# SCH_Flight-Computer-V5_2024-08-09.net
KiCad netlist of a schematic drawn in EasyEDA
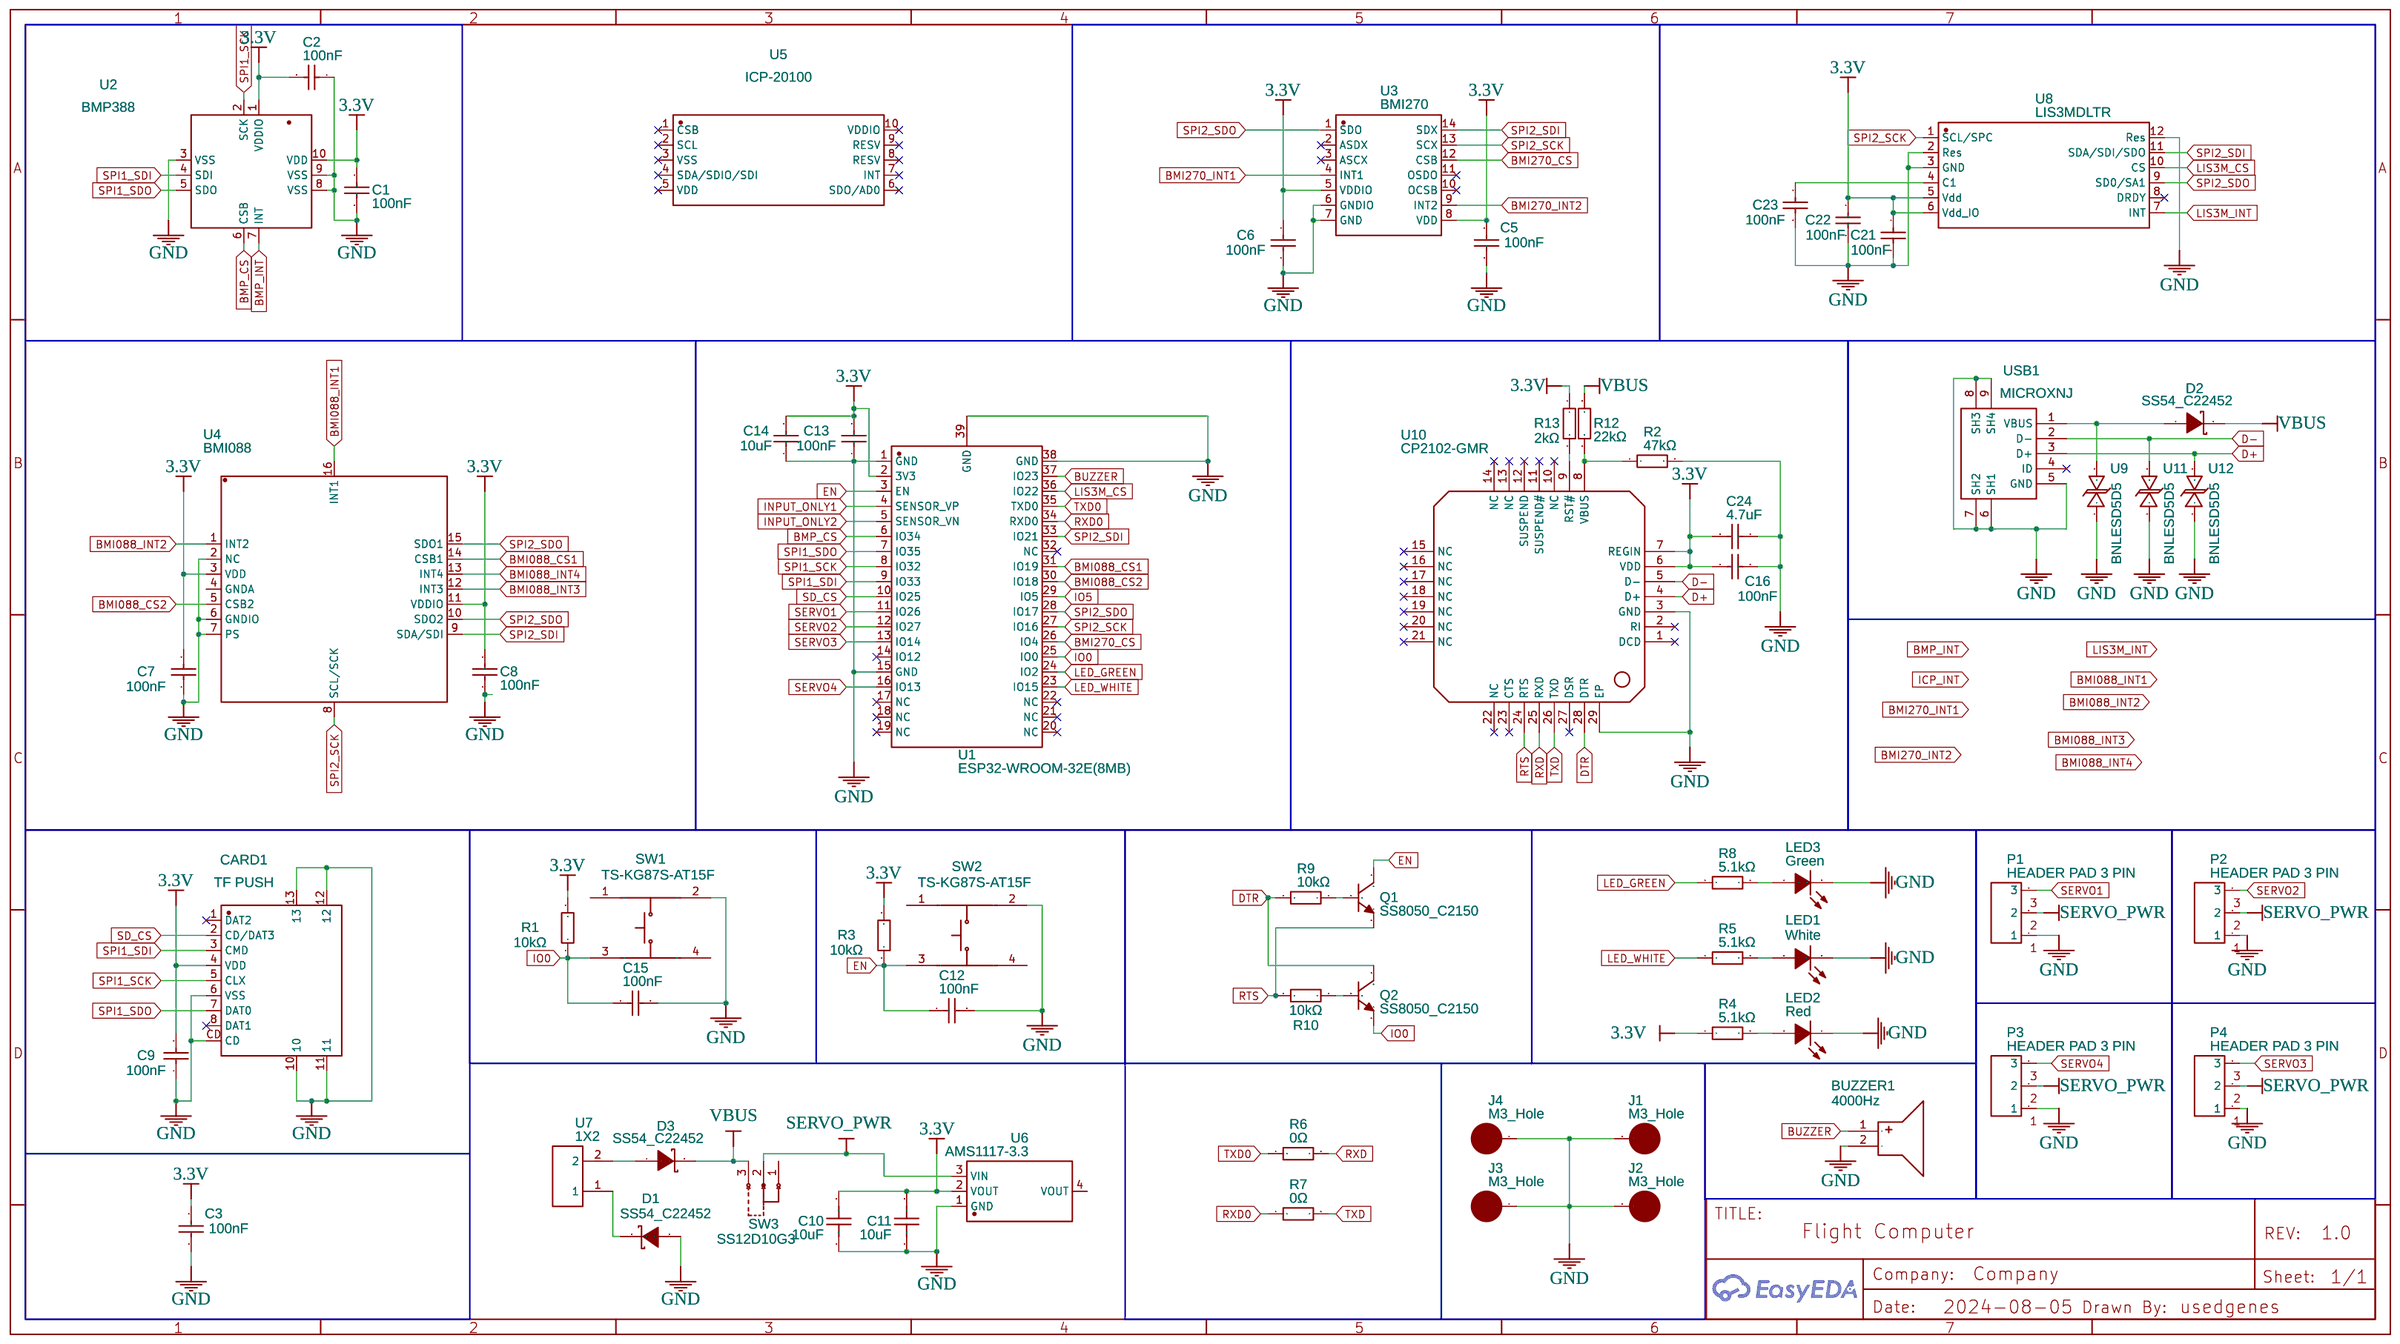
[diagram p0: schematic sheet]

(export (version "E")
  (design (tool "Eeschema 10.0.6"))
  (components
    (comp (ref "BUZZER1")
      (value "4000Hz")
      (fields
        (field (name "Manufacturer Part") "SKY-1475-0540-45P7.6")
        (field (name "Manufacturer") "S&S(海旭)")
      )
      (libsource (lib "") (part "SKY-1475-0540-45P7.6"))
    )
    (comp (ref "C1")
      (value "100nF")
      (fields
        (field (name "Manufacturer Part") "CL05B104KO5NNNC")
        (field (name "Manufacturer") "SAMSUNG(三星)")
      )
      (libsource (lib "") (part "CL05B104KO5NNNC_1"))
    )
    (comp (ref "C2")
      (value "100nF")
      (fields
        (field (name "Manufacturer Part") "CL05B104KO5NNNC")
        (field (name "Manufacturer") "SAMSUNG(三星)")
      )
      (libsource (lib "") (part "CL05B104KO5NNNC_3"))
    )
    (comp (ref "C3")
      (value "100nF")
      (fields
        (field (name "Manufacturer Part") "CL05B104KO5NNNC")
        (field (name "Manufacturer") "SAMSUNG(三星)")
      )
      (libsource (lib "") (part "CL05B104KO5NNNC_1"))
    )
    (comp (ref "C5")
      (value "100nF")
      (fields
        (field (name "Manufacturer Part") "CL05B104KO5NNNC")
        (field (name "Manufacturer") "SAMSUNG(三星)")
      )
      (libsource (lib "") (part "CL05B104KO5NNNC_1"))
    )
    (comp (ref "C6")
      (value "100nF")
      (fields
        (field (name "Manufacturer Part") "CL05B104KO5NNNC")
        (field (name "Manufacturer") "SAMSUNG(三星)")
      )
      (libsource (lib "") (part "CL05B104KO5NNNC_1"))
    )
    (comp (ref "C7")
      (value "100nF")
      (fields
        (field (name "Manufacturer Part") "CL05B104KO5NNNC")
        (field (name "Manufacturer") "SAMSUNG(三星)")
      )
      (libsource (lib "") (part "CL05B104KO5NNNC_1"))
    )
    (comp (ref "C8")
      (value "100nF")
      (fields
        (field (name "Manufacturer Part") "CL05B104KO5NNNC")
        (field (name "Manufacturer") "SAMSUNG(三星)")
      )
      (libsource (lib "") (part "CL05B104KO5NNNC_1"))
    )
    (comp (ref "C9")
      (value "100nF")
      (fields
        (field (name "Manufacturer Part") "CL05B104KO5NNNC")
        (field (name "Manufacturer") "SAMSUNG(三星)")
      )
      (libsource (lib "") (part "CL05B104KO5NNNC_1"))
    )
    (comp (ref "C10")
      (value "10uF")
      (fields
        (field (name "Manufacturer Part") "CL10A106KP8NNNC")
        (field (name "Manufacturer") "SAMSUNG(三星)")
      )
      (libsource (lib "") (part "CL10A106KP8NNNC"))
    )
    (comp (ref "C11")
      (value "10uF")
      (fields
        (field (name "Manufacturer Part") "CL10A106KP8NNNC")
        (field (name "Manufacturer") "SAMSUNG(三星)")
      )
      (libsource (lib "") (part "CL10A106KP8NNNC"))
    )
    (comp (ref "C12")
      (value "100nF")
      (fields
        (field (name "Manufacturer Part") "CL05B104KO5NNNC")
        (field (name "Manufacturer") "SAMSUNG(三星)")
      )
      (libsource (lib "") (part "CL05B104KO5NNNC_2"))
    )
    (comp (ref "C13")
      (value "100nF")
      (fields
        (field (name "Manufacturer Part") "CL05B104KO5NNNC")
        (field (name "Manufacturer") "SAMSUNG(三星)")
      )
      (libsource (lib "") (part "CL05B104KO5NNNC_1"))
    )
    (comp (ref "C14")
      (value "10uF")
      (fields
        (field (name "Manufacturer Part") "CL05A106MQ5NUNC")
        (field (name "Manufacturer") "SAMSUNG(三星)")
      )
      (libsource (lib "") (part "CL05A106MQ5NUNC"))
    )
    (comp (ref "C15")
      (value "100nF")
      (fields
        (field (name "Manufacturer Part") "CL05B104KO5NNNC")
        (field (name "Manufacturer") "SAMSUNG(三星)")
      )
      (libsource (lib "") (part "CL05B104KO5NNNC_2"))
    )
    (comp (ref "C16")
      (value "100nF")
      (fields
        (field (name "Manufacturer Part") "CL05B104KO5NNNC")
        (field (name "Manufacturer") "SAMSUNG(三星)")
      )
      (libsource (lib "") (part "CL05B104KO5NNNC_2"))
    )
    (comp (ref "C21")
      (value "100nF")
      (fields
        (field (name "Manufacturer Part") "CL05B104KO5NNNC")
        (field (name "Manufacturer") "SAMSUNG(三星)")
      )
      (libsource (lib "") (part "CL05B104KO5NNNC"))
    )
    (comp (ref "C22")
      (value "100nF")
      (fields
        (field (name "Manufacturer Part") "CL05B104KO5NNNC")
        (field (name "Manufacturer") "SAMSUNG(三星)")
      )
      (libsource (lib "") (part "CL05B104KO5NNNC"))
    )
    (comp (ref "C23")
      (value "100nF")
      (fields
        (field (name "Manufacturer Part") "CL05B104KO5NNNC")
        (field (name "Manufacturer") "SAMSUNG(三星)")
      )
      (libsource (lib "") (part "CL05B104KO5NNNC"))
    )
    (comp (ref "C24")
      (value "4.7uF")
      (fields
        (field (name "Manufacturer Part") "CL05A475MP5NRNC")
        (field (name "Manufacturer") "SAMSUNG(三星)")
      )
      (libsource (lib "") (part "CL05A475MP5NRNC"))
    )
    (comp (ref "CARD1")
      (value "TF PUSH")
      (fields (field (name "Manufacturer") "SHOU HAN(首韩)"))
      (libsource (lib "") (part "TF PUSH"))
    )
    (comp (ref "D1")
      (value "SS54_C22452")
      (fields (field (name "Manufacturer Part") "SS54") (field (name "Manufacturer") "MDD(辰达半导体)"))
      (libsource (lib "") (part "SS54_C22452"))
    )
    (comp (ref "D2")
      (value "SS54_C22452")
      (fields (field (name "Manufacturer Part") "SS54") (field (name "Manufacturer") "MDD(辰达半导体)"))
      (libsource (lib "") (part "SS54_C22452_1"))
    )
    (comp (ref "D3")
      (value "SS54_C22452")
      (fields (field (name "Manufacturer Part") "SS54") (field (name "Manufacturer") "MDD(辰达半导体)"))
      (libsource (lib "") (part "SS54_C22452_1"))
    )
    (comp (ref "J1") (value "M3_Hole") (libsource (lib "") (part "SCREW-MOUNTING-HOLE-3MM")))
    (comp (ref "J2") (value "M3_Hole") (libsource (lib "") (part "SCREW-MOUNTING-HOLE-3MM")))
    (comp (ref "J3") (value "M3_Hole") (libsource (lib "") (part "SCREW-MOUNTING-HOLE-3MM_1")))
    (comp (ref "J4") (value "M3_Hole") (libsource (lib "") (part "SCREW-MOUNTING-HOLE-3MM_1")))
    (comp (ref "LED1")
      (value "White")
      (fields (field (name "Manufacturer Part") "KT-0603白灯") (field (name "Manufacturer") "KENTO"))
      (libsource (lib "") (part "0603White light_C2290"))
    )
    (comp (ref "LED2")
      (value "Red")
      (fields (field (name "Manufacturer Part") "KT-0603R") (field (name "Manufacturer") "KENTO"))
      (libsource (lib "") (part "KT-0603R"))
    )
    (comp (ref "LED3")
      (value "Green")
      (fields (field (name "Manufacturer Part") "KT-0805G") (field (name "Manufacturer") "KENTO"))
      (libsource (lib "") (part "0805G (Green)"))
    )
    (comp (ref "P1")
      (value "HEADER PAD 3 PIN")
      (fields
        (field (name "Manufacturer Part") "Female headerHDR1X8-2.54")
        (field (name "Manufacturer") "BOOMELE")
      )
      (libsource (lib "") (part "HEADER PAD 3 PIN"))
    )
    (comp (ref "P2")
      (value "HEADER PAD 3 PIN")
      (fields
        (field (name "Manufacturer Part") "Female headerHDR1X8-2.54")
        (field (name "Manufacturer") "BOOMELE")
      )
      (libsource (lib "") (part "HEADER PAD 3 PIN"))
    )
    (comp (ref "P3")
      (value "HEADER PAD 3 PIN")
      (fields
        (field (name "Manufacturer Part") "Female headerHDR1X8-2.54")
        (field (name "Manufacturer") "BOOMELE")
      )
      (libsource (lib "") (part "HEADER PAD 3 PIN"))
    )
    (comp (ref "P4")
      (value "HEADER PAD 3 PIN")
      (fields
        (field (name "Manufacturer Part") "Female headerHDR1X8-2.54")
        (field (name "Manufacturer") "BOOMELE")
      )
      (libsource (lib "") (part "HEADER PAD 3 PIN"))
    )
    (comp (ref "Q1")
      (value "SS8050_C2150")
      (fields (field (name "Manufacturer Part") "SS8050") (field (name "Manufacturer") "CJ(江苏长电/长晶)"))
      (libsource (lib "") (part "SS8050_C2150"))
    )
    (comp (ref "Q2")
      (value "SS8050_C2150")
      (fields (field (name "Manufacturer Part") "SS8050") (field (name "Manufacturer") "CJ(江苏长电/长晶)"))
      (libsource (lib "") (part "SS8050_C2150"))
    )
    (comp (ref "R1")
      (value "10kΩ")
      (fields
        (field (name "Manufacturer Part") "0603WAF1002T5E")
        (field (name "Manufacturer") "UNI-ROYAL(厚声)")
      )
      (libsource (lib "") (part "0603WAF1002T5E_1"))
    )
    (comp (ref "R2")
      (value "47kΩ")
      (fields
        (field (name "Manufacturer Part") "0402WGF4702TCE")
        (field (name "Manufacturer") "UNI-ROYAL(厚声)")
      )
      (libsource (lib "") (part "0402WGF4702TCE"))
    )
    (comp (ref "R3")
      (value "10kΩ")
      (fields
        (field (name "Manufacturer Part") "0603WAF1002T5E")
        (field (name "Manufacturer") "UNI-ROYAL(厚声)")
      )
      (libsource (lib "") (part "0603WAF1002T5E_1"))
    )
    (comp (ref "R4")
      (value "5.1kΩ")
      (fields
        (field (name "Manufacturer Part") "0402WGF5101TCE")
        (field (name "Manufacturer") "UNI-ROYAL(厚声)")
      )
      (libsource (lib "") (part "0402WGF5101TCE"))
    )
    (comp (ref "R5")
      (value "5.1kΩ")
      (fields
        (field (name "Manufacturer Part") "0402WGF5101TCE")
        (field (name "Manufacturer") "UNI-ROYAL(厚声)")
      )
      (libsource (lib "") (part "0402WGF5101TCE"))
    )
    (comp (ref "R6")
      (value "0Ω")
      (fields
        (field (name "Manufacturer Part") "1206W4F0000T5E")
        (field (name "Manufacturer") "UNI-ROYAL(厚声)")
      )
      (libsource (lib "") (part "1206W4F0000T5E"))
    )
    (comp (ref "R7")
      (value "0Ω")
      (fields
        (field (name "Manufacturer Part") "1206W4F0000T5E")
        (field (name "Manufacturer") "UNI-ROYAL(厚声)")
      )
      (libsource (lib "") (part "1206W4F0000T5E"))
    )
    (comp (ref "R8")
      (value "5.1kΩ")
      (fields
        (field (name "Manufacturer Part") "0402WGF5101TCE")
        (field (name "Manufacturer") "UNI-ROYAL(厚声)")
      )
      (libsource (lib "") (part "0402WGF5101TCE"))
    )
    (comp (ref "R9")
      (value "10kΩ")
      (fields
        (field (name "Manufacturer Part") "0603WAF1002T5E")
        (field (name "Manufacturer") "UNI-ROYAL(厚声)")
      )
      (libsource (lib "") (part "0603WAF1002T5E_2"))
    )
    (comp (ref "R10")
      (value "10kΩ")
      (fields
        (field (name "Manufacturer Part") "0603WAF1002T5E")
        (field (name "Manufacturer") "UNI-ROYAL(厚声)")
      )
      (libsource (lib "") (part "0603WAF1002T5E"))
    )
    (comp (ref "R12")
      (value "22kΩ")
      (fields
        (field (name "Manufacturer Part") "0402WGF2202TCE")
        (field (name "Manufacturer") "UNI-ROYAL(厚声)")
      )
      (libsource (lib "") (part "0402WGF2202TCE"))
    )
    (comp (ref "R13")
      (value "2kΩ")
      (fields
        (field (name "Manufacturer Part") "0402WGF2001TCE")
        (field (name "Manufacturer") "UNI-ROYAL(厚声)")
      )
      (libsource (lib "") (part "0402WGF2001TCE"))
    )
    (comp (ref "SW1")
      (value "TS-KG87S-AT15F")
      (fields (field (name "Manufacturer") "HANBO(汉博)"))
      (libsource (lib "") (part "TS-KG87S-AT15F"))
    )
    (comp (ref "SW2")
      (value "TS-KG87S-AT15F")
      (fields (field (name "Manufacturer") "HANBO(汉博)"))
      (libsource (lib "") (part "TS-KG87S-AT15F"))
    )
    (comp (ref "SW3")
      (value "SS12D10G3")
      (fields (field (name "Manufacturer") "SHOU HAN(首韩)"))
      (libsource (lib "") (part "SS12D10G3"))
    )
    (comp (ref "U1")
      (value "ESP32-WROOM-32E(8MB)")
      (fields
        (field (name "Manufacturer Part") "ESP32-WROOM-32E-N8")
        (field (name "Manufacturer") "ESPRESSIF(乐鑫)")
      )
      (libsource (lib "") (part "ESP32-WROOM-32E(8MB)"))
    )
    (comp (ref "U2")
      (value "BMP388")
      (fields (field (name "Manufacturer") "Bosch(博世)"))
      (libsource (lib "") (part "BMP388"))
    )
    (comp (ref "U3")
      (value "BMI270")
      (fields (field (name "Manufacturer") "Bosch(博世)"))
      (libsource (lib "") (part "BMI270"))
    )
    (comp (ref "U4")
      (value "BMI088")
      (fields (field (name "Manufacturer") "Bosch(博世)"))
      (libsource (lib "") (part "BMI088"))
    )
    (comp (ref "U5")
      (value "ICP-20100")
      (fields (field (name "Manufacturer") "TDK"))
      (libsource (lib "") (part "ICP-20100"))
    )
    (comp (ref "U6")
      (value "AMS1117-3.3")
      (fields (field (name "Manufacturer") "AMS"))
      (libsource (lib "") (part "AMS1117-3.3"))
    )
    (comp (ref "U7") (value "1X2") (libsource (lib "") (part "1X2")))
    (comp (ref "U8")
      (value "LIS3MDLTR")
      (fields (field (name "Manufacturer") "ST(意法半导体)"))
      (libsource (lib "") (part "LIS3MDLTR"))
    )
    (comp (ref "U9")
      (value "BNLESD5D5")
      (fields
        (field (name "Manufacturer Part") "BNLESD5D5.0CT1G")
        (field (name "Manufacturer") "BORN(伯恩半导体)")
      )
      (libsource (lib "") (part "BNLESD5D5.0CT1G"))
    )
    (comp (ref "U10")
      (value "CP2102-GMR")
      (fields (field (name "Manufacturer") "SKYWORKS/SILICON LABS(芯科)"))
      (libsource (lib "") (part "CP2102-GMR"))
    )
    (comp (ref "U11")
      (value "BNLESD5D5")
      (fields
        (field (name "Manufacturer Part") "BNLESD5D5.0CT1G")
        (field (name "Manufacturer") "BORN(伯恩半导体)")
      )
      (libsource (lib "") (part "BNLESD5D5.0CT1G"))
    )
    (comp (ref "U12")
      (value "BNLESD5D5")
      (fields
        (field (name "Manufacturer Part") "BNLESD5D5.0CT1G")
        (field (name "Manufacturer") "BORN(伯恩半导体)")
      )
      (libsource (lib "") (part "BNLESD5D5.0CT1G"))
    )
    (comp (ref "USB1")
      (value "MICROXNJ")
      (fields (field (name "Manufacturer Part") "MicroXNJ") (field (name "Manufacturer") "SHOU HAN(首韩)"))
      (libsource (lib "") (part "MICROXNJ"))
    )
  )
  (nets
    (net (code "1") (name "3.3V") (class "Default")
      (node (ref "C1") (pin "2") (pinfunction "2_2") (pintype "input"))
      (node (ref "C10") (pin "2") (pinfunction "2_2") (pintype "unspecified"))
      (node (ref "C11") (pin "2") (pinfunction "2_2") (pintype "unspecified"))
      (node (ref "C13") (pin "2") (pinfunction "2_2") (pintype "input"))
      (node (ref "C14") (pin "2") (pinfunction "2_2") (pintype "input"))
      (node (ref "C16") (pin "1") (pinfunction "1_1") (pintype "input"))
      (node (ref "C2") (pin "2") (pinfunction "2_2") (pintype "input"))
      (node (ref "C21") (pin "1") (pinfunction "1_1") (pintype "input"))
      (node (ref "C22") (pin "1") (pinfunction "1_1") (pintype "input"))
      (node (ref "C24") (pin "1") (pinfunction "1_1") (pintype "input"))
      (node (ref "C3") (pin "2") (pinfunction "2_2") (pintype "input"))
      (node (ref "C5") (pin "2") (pinfunction "2_2") (pintype "input"))
      (node (ref "C6") (pin "2") (pinfunction "2_2") (pintype "input"))
      (node (ref "C7") (pin "2") (pinfunction "2_2") (pintype "input"))
      (node (ref "C8") (pin "2") (pinfunction "2_2") (pintype "input"))
      (node (ref "C9") (pin "2") (pinfunction "2_2") (pintype "input"))
      (node (ref "CARD1") (pin "4") (pinfunction "VDD_4") (pintype "unspecified"))
      (node (ref "R1") (pin "2") (pinfunction "2_2") (pintype "input"))
      (node (ref "R13") (pin "1") (pinfunction "1_1") (pintype "input"))
      (node (ref "R3") (pin "2") (pinfunction "2_2") (pintype "input"))
      (node (ref "R4") (pin "1") (pinfunction "1_1") (pintype "input"))
      (node (ref "U1") (pin "2") (pinfunction "3V3_2") (pintype "unspecified"))
      (node (ref "U10") (pin "6") (pinfunction "VDD_6") (pintype "unspecified"))
      (node (ref "U10") (pin "7") (pinfunction "REGIN_7") (pintype "unspecified"))
      (node (ref "U2") (pin "1") (pinfunction "VDDIO_1") (pintype "unspecified"))
      (node (ref "U2") (pin "10") (pinfunction "VDD_10") (pintype "unspecified"))
      (node (ref "U3") (pin "5") (pinfunction "VDDIO_5") (pintype "unspecified"))
      (node (ref "U3") (pin "8") (pinfunction "VDD_8") (pintype "unspecified"))
      (node (ref "U4") (pin "11") (pinfunction "VDDIO_11") (pintype "unspecified"))
      (node (ref "U4") (pin "3") (pinfunction "VDD_3") (pintype "unspecified"))
      (node (ref "U6") (pin "2") (pinfunction "VOUT_2") (pintype "unspecified"))
      (node (ref "U8") (pin "5") (pinfunction "Vdd_5") (pintype "unspecified"))
      (node (ref "U8") (pin "6") (pinfunction "Vdd_IO_6") (pintype "unspecified"))
    )
    (net (code "2") (name "BMI088_CS1") (class "Default")
      (node (ref "U1") (pin "31") (pinfunction "IO19_31") (pintype "unspecified"))
      (node (ref "U4") (pin "14") (pinfunction "CSB1_14") (pintype "unspecified"))
    )
    (net (code "3") (name "BMI088_CS2") (class "Default")
      (node (ref "U1") (pin "30") (pinfunction "IO18_30") (pintype "unspecified"))
      (node (ref "U4") (pin "5") (pinfunction "CSB2_5") (pintype "unspecified"))
    )
    (net (code "4") (name "BMI088_INT1") (class "Default")
      (node (ref "U4") (pin "16") (pinfunction "INT1_16") (pintype "unspecified"))
    )
    (net (code "5") (name "BMI088_INT2") (class "Default")
      (node (ref "U4") (pin "1") (pinfunction "INT2_1") (pintype "unspecified"))
    )
    (net (code "6") (name "BMI088_INT3") (class "Default")
      (node (ref "U4") (pin "12") (pinfunction "INT3_12") (pintype "unspecified"))
    )
    (net (code "7") (name "BMI088_INT4") (class "Default")
      (node (ref "U4") (pin "13") (pinfunction "INT4_13") (pintype "unspecified"))
    )
    (net (code "8") (name "BMI270_CS") (class "Default")
      (node (ref "U1") (pin "26") (pinfunction "IO4_26") (pintype "unspecified"))
      (node (ref "U3") (pin "12") (pinfunction "CSB_12") (pintype "unspecified"))
    )
    (net (code "9") (name "BMI270_INT1") (class "Default")
      (node (ref "U3") (pin "4") (pinfunction "INT1_4") (pintype "unspecified"))
    )
    (net (code "10") (name "BMI270_INT2") (class "Default")
      (node (ref "U3") (pin "9") (pinfunction "INT2_9") (pintype "unspecified"))
    )
    (net (code "11") (name "BMP_CS") (class "Default")
      (node (ref "U1") (pin "6") (pinfunction "IO34_6") (pintype "unspecified"))
      (node (ref "U2") (pin "6") (pinfunction "CSB_6") (pintype "unspecified"))
    )
    (net (code "12") (name "BMP_INT") (class "Default")
      (node (ref "U2") (pin "7") (pinfunction "INT_7") (pintype "unspecified"))
    )
    (net (code "13") (name "BUZZER") (class "Default")
      (node (ref "BUZZER1") (pin "1") (pinfunction "+_1") (pintype "unspecified"))
      (node (ref "U1") (pin "37") (pinfunction "IO23_37") (pintype "unspecified"))
    )
    (net (code "14") (name "D+") (class "Default")
      (node (ref "U10") (pin "4") (pinfunction "D+_4") (pintype "unspecified"))
      (node (ref "U12") (pin "2") (pinfunction "2_2") (pintype "unspecified"))
      (node (ref "USB1") (pin "3") (pinfunction "D+_3") (pintype "unspecified"))
    )
    (net (code "15") (name "D-") (class "Default")
      (node (ref "U10") (pin "5") (pinfunction "D-_5") (pintype "unspecified"))
      (node (ref "U11") (pin "2") (pinfunction "2_2") (pintype "unspecified"))
      (node (ref "USB1") (pin "2") (pinfunction "D-_2") (pintype "unspecified"))
    )
    (net (code "16") (name "DTR") (class "Default")
      (node (ref "Q2") (pin "3") (pinfunction "C_3") (pintype "unspecified"))
      (node (ref "R9") (pin "2") (pinfunction "2_2") (pintype "input"))
      (node (ref "U10") (pin "28") (pinfunction "DTR_28") (pintype "unspecified"))
    )
    (net (code "17") (name "EN") (class "Default")
      (node (ref "C12") (pin "1") (pinfunction "1_1") (pintype "input"))
      (node (ref "Q1") (pin "3") (pinfunction "C_3") (pintype "unspecified"))
      (node (ref "R3") (pin "1") (pinfunction "1_1") (pintype "input"))
      (node (ref "SW2") (pin "3") (pinfunction "3_3") (pintype "unspecified"))
      (node (ref "U1") (pin "3") (pinfunction "EN_3") (pintype "unspecified"))
    )
    (net (code "18") (name "GND") (class "Default")
      (node (ref "BUZZER1") (pin "2") (pinfunction "-_2") (pintype "unspecified"))
      (node (ref "C1") (pin "1") (pinfunction "1_1") (pintype "input"))
      (node (ref "C10") (pin "1") (pinfunction "1_1") (pintype "unspecified"))
      (node (ref "C11") (pin "1") (pinfunction "1_1") (pintype "unspecified"))
      (node (ref "C12") (pin "2") (pinfunction "2_2") (pintype "input"))
      (node (ref "C13") (pin "1") (pinfunction "1_1") (pintype "input"))
      (node (ref "C14") (pin "1") (pinfunction "1_1") (pintype "input"))
      (node (ref "C15") (pin "2") (pinfunction "2_2") (pintype "input"))
      (node (ref "C16") (pin "2") (pinfunction "2_2") (pintype "input"))
      (node (ref "C2") (pin "1") (pinfunction "1_1") (pintype "input"))
      (node (ref "C21") (pin "2") (pinfunction "2_2") (pintype "input"))
      (node (ref "C22") (pin "2") (pinfunction "2_2") (pintype "input"))
      (node (ref "C23") (pin "2") (pinfunction "2_2") (pintype "input"))
      (node (ref "C24") (pin "2") (pinfunction "2_2") (pintype "input"))
      (node (ref "C3") (pin "1") (pinfunction "1_1") (pintype "input"))
      (node (ref "C5") (pin "1") (pinfunction "1_1") (pintype "input"))
      (node (ref "C6") (pin "1") (pinfunction "1_1") (pintype "input"))
      (node (ref "C7") (pin "1") (pinfunction "1_1") (pintype "input"))
      (node (ref "C8") (pin "1") (pinfunction "1_1") (pintype "input"))
      (node (ref "C9") (pin "1") (pinfunction "1_1") (pintype "input"))
      (node (ref "CARD1") (pin "10") (pinfunction "10_10") (pintype "unspecified"))
      (node (ref "CARD1") (pin "11") (pinfunction "11_11") (pintype "unspecified"))
      (node (ref "CARD1") (pin "12") (pinfunction "12_12") (pintype "unspecified"))
      (node (ref "CARD1") (pin "13") (pinfunction "13_13") (pintype "unspecified"))
      (node (ref "CARD1") (pin "6") (pinfunction "VSS_6") (pintype "unspecified"))
      (node (ref "CARD1") (pin "CD") (pinfunction "CD_CD") (pintype "unspecified"))
      (node (ref "D1") (pin "1") (pinfunction "A_1") (pintype "unspecified"))
      (node (ref "J1") (pin "1") (pinfunction "1_1") (pintype "unspecified"))
      (node (ref "J2") (pin "1") (pinfunction "1_1") (pintype "unspecified"))
      (node (ref "J3") (pin "1") (pinfunction "1_1") (pintype "unspecified"))
      (node (ref "J4") (pin "1") (pinfunction "1_1") (pintype "unspecified"))
      (node (ref "LED1") (pin "2") (pinfunction "K_2") (pintype "unspecified"))
      (node (ref "LED2") (pin "1") (pinfunction "K_1") (pintype "unspecified"))
      (node (ref "LED3") (pin "2") (pinfunction "K_2") (pintype "unspecified"))
      (node (ref "P1") (pin "1") (pinfunction "1_1") (pintype "unspecified"))
      (node (ref "P2") (pin "1") (pinfunction "1_1") (pintype "unspecified"))
      (node (ref "P3") (pin "1") (pinfunction "1_1") (pintype "unspecified"))
      (node (ref "P4") (pin "1") (pinfunction "1_1") (pintype "unspecified"))
      (node (ref "R2") (pin "2") (pinfunction "2_2") (pintype "input"))
      (node (ref "SW1") (pin "2") (pinfunction "2_2") (pintype "unspecified"))
      (node (ref "SW2") (pin "2") (pinfunction "2_2") (pintype "unspecified"))
      (node (ref "U1") (pin "1") (pinfunction "GND_1") (pintype "unspecified"))
      (node (ref "U1") (pin "15") (pinfunction "GND_15") (pintype "unspecified"))
      (node (ref "U1") (pin "38") (pinfunction "GND_38") (pintype "unspecified"))
      (node (ref "U1") (pin "39") (pinfunction "GND_39") (pintype "unspecified"))
      (node (ref "U10") (pin "29") (pinfunction "EP_29") (pintype "unspecified"))
      (node (ref "U10") (pin "3") (pinfunction "GND_3") (pintype "unspecified"))
      (node (ref "U11") (pin "1") (pinfunction "1_1") (pintype "unspecified"))
      (node (ref "U12") (pin "1") (pinfunction "1_1") (pintype "unspecified"))
      (node (ref "U2") (pin "3") (pinfunction "VSS_3") (pintype "unspecified"))
      (node (ref "U2") (pin "8") (pinfunction "VSS_8") (pintype "unspecified"))
      (node (ref "U2") (pin "9") (pinfunction "VSS_9") (pintype "unspecified"))
      (node (ref "U3") (pin "6") (pinfunction "GNDIO_6") (pintype "unspecified"))
      (node (ref "U3") (pin "7") (pinfunction "GND_7") (pintype "unspecified"))
      (node (ref "U4") (pin "2") (pinfunction "NC_2") (pintype "unspecified"))
      (node (ref "U4") (pin "6") (pinfunction "GNDIO_6") (pintype "unspecified"))
      (node (ref "U4") (pin "7") (pinfunction "PS_7") (pintype "unspecified"))
      (node (ref "U6") (pin "1") (pinfunction "GND_1") (pintype "unspecified"))
      (node (ref "U8") (pin "12") (pinfunction "Res_12") (pintype "unspecified"))
      (node (ref "U8") (pin "2") (pinfunction "Res_2") (pintype "unspecified"))
      (node (ref "U8") (pin "3") (pinfunction "GND_3") (pintype "unspecified"))
      (node (ref "U9") (pin "1") (pinfunction "1_1") (pintype "unspecified"))
      (node (ref "USB1") (pin "5") (pinfunction "GND_5") (pintype "unspecified"))
      (node (ref "USB1") (pin "6") (pinfunction "SH1_6") (pintype "unspecified"))
      (node (ref "USB1") (pin "7") (pinfunction "SH2_7") (pintype "unspecified"))
      (node (ref "USB1") (pin "8") (pinfunction "SH3_8") (pintype "unspecified"))
      (node (ref "USB1") (pin "9") (pinfunction "SH4_9") (pintype "unspecified"))
    )
    (net (code "20") (name "INPUT_ONLY1") (class "Default")
      (node (ref "U1") (pin "4") (pinfunction "SENSOR_VP_4") (pintype "unspecified"))
    )
    (net (code "21") (name "INPUT_ONLY2") (class "Default")
      (node (ref "U1") (pin "5") (pinfunction "SENSOR_VN_5") (pintype "unspecified"))
    )
    (net (code "22") (name "IO0") (class "Default")
      (node (ref "C15") (pin "1") (pinfunction "1_1") (pintype "input"))
      (node (ref "Q2") (pin "2") (pinfunction "E_2") (pintype "unspecified"))
      (node (ref "R1") (pin "1") (pinfunction "1_1") (pintype "input"))
      (node (ref "SW1") (pin "3") (pinfunction "3_3") (pintype "unspecified"))
      (node (ref "U1") (pin "25") (pinfunction "IO0_25") (pintype "unspecified"))
    )
    (net (code "23") (name "IO5") (class "Default")
      (node (ref "U1") (pin "29") (pinfunction "IO5_29") (pintype "unspecified"))
    )
    (net (code "24") (name "LED_GREEN") (class "Default")
      (node (ref "R8") (pin "1") (pinfunction "1_1") (pintype "input"))
      (node (ref "U1") (pin "24") (pinfunction "IO2_24") (pintype "unspecified"))
    )
    (net (code "25") (name "LED_WHITE") (class "Default")
      (node (ref "R5") (pin "1") (pinfunction "1_1") (pintype "input"))
      (node (ref "U1") (pin "23") (pinfunction "IO15_23") (pintype "unspecified"))
    )
    (net (code "26") (name "LIS3M_CS") (class "Default")
      (node (ref "U1") (pin "36") (pinfunction "IO22_36") (pintype "unspecified"))
      (node (ref "U8") (pin "10") (pinfunction "CS_10") (pintype "unspecified"))
    )
    (net (code "27") (name "LIS3M_INT") (class "Default")
      (node (ref "U8") (pin "7") (pinfunction "INT_7") (pintype "unspecified"))
    )
    (net (code "28") (name "Net-(D1-K)") (class "Default")
      (node (ref "D1") (pin "2") (pinfunction "K_2") (pintype "unspecified"))
      (node (ref "U7") (pin "1") (pinfunction "1_1") (pintype "unspecified"))
    )
    (net (code "29") (name "Net-(D2-A)") (class "Default")
      (node (ref "D2") (pin "1") (pinfunction "A_1") (pintype "unspecified"))
      (node (ref "U9") (pin "2") (pinfunction "2_2") (pintype "unspecified"))
      (node (ref "USB1") (pin "1") (pinfunction "VBUS_1") (pintype "unspecified"))
    )
    (net (code "30") (name "Net-(D3-A)") (class "Default")
      (node (ref "D3") (pin "1") (pinfunction "A_1") (pintype "unspecified"))
      (node (ref "U7") (pin "2") (pinfunction "2_2") (pintype "unspecified"))
    )
    (net (code "31") (name "Net-(LED1-A)") (class "Default")
      (node (ref "LED1") (pin "1") (pinfunction "A_1") (pintype "unspecified"))
      (node (ref "R5") (pin "2") (pinfunction "2_2") (pintype "input"))
    )
    (net (code "32") (name "Net-(LED2-A)") (class "Default")
      (node (ref "LED2") (pin "2") (pinfunction "A_2") (pintype "unspecified"))
      (node (ref "R4") (pin "2") (pinfunction "2_2") (pintype "input"))
    )
    (net (code "33") (name "Net-(LED3-A)") (class "Default")
      (node (ref "LED3") (pin "1") (pinfunction "A_1") (pintype "unspecified"))
      (node (ref "R8") (pin "2") (pinfunction "2_2") (pintype "input"))
    )
    (net (code "34") (name "Net-(Q1-B)") (class "Default")
      (node (ref "Q1") (pin "1") (pinfunction "B_1") (pintype "unspecified"))
      (node (ref "R9") (pin "1") (pinfunction "1_1") (pintype "input"))
    )
    (net (code "35") (name "Net-(Q2-B)") (class "Default")
      (node (ref "Q2") (pin "1") (pinfunction "B_1") (pintype "unspecified"))
      (node (ref "R10") (pin "2") (pinfunction "2_2") (pintype "input"))
    )
    (net (code "36") (name "Net-(U8-C1)") (class "Default")
      (node (ref "C23") (pin "1") (pinfunction "1_1") (pintype "input"))
      (node (ref "U8") (pin "4") (pinfunction "C1_4") (pintype "unspecified"))
    )
    (net (code "37") (name "Net-(U10-RST#)") (class "Default")
      (node (ref "R13") (pin "2") (pinfunction "2_2") (pintype "input"))
      (node (ref "U10") (pin "9") (pinfunction "RST#_9") (pintype "unspecified"))
    )
    (net (code "38") (name "Net-(U10-VBUS)") (class "Default")
      (node (ref "R12") (pin "1") (pinfunction "1_1") (pintype "input"))
      (node (ref "R2") (pin "1") (pinfunction "1_1") (pintype "input"))
      (node (ref "U10") (pin "8") (pinfunction "VBUS_8") (pintype "unspecified"))
    )
    (net (code "39") (name "RTS") (class "Default")
      (node (ref "Q1") (pin "2") (pinfunction "E_2") (pintype "unspecified"))
      (node (ref "R10") (pin "1") (pinfunction "1_1") (pintype "input"))
      (node (ref "U10") (pin "24") (pinfunction "RTS_24") (pintype "unspecified"))
    )
    (net (code "40") (name "RXD") (class "Default")
      (node (ref "R6") (pin "2") (pinfunction "2_2") (pintype "input"))
      (node (ref "U10") (pin "25") (pinfunction "RXD_25") (pintype "unspecified"))
    )
    (net (code "41") (name "RXD0") (class "Default")
      (node (ref "R7") (pin "1") (pinfunction "1_1") (pintype "input"))
      (node (ref "U1") (pin "34") (pinfunction "RXD0_34") (pintype "unspecified"))
    )
    (net (code "42") (name "SD_CS") (class "Default")
      (node (ref "CARD1") (pin "2") (pinfunction "CD/DAT3_2") (pintype "unspecified"))
      (node (ref "U1") (pin "10") (pinfunction "IO25_10") (pintype "unspecified"))
    )
    (net (code "43") (name "SERVO1") (class "Default")
      (node (ref "P1") (pin "3") (pinfunction "3_3") (pintype "unspecified"))
      (node (ref "U1") (pin "11") (pinfunction "IO26_11") (pintype "unspecified"))
    )
    (net (code "44") (name "SERVO2") (class "Default")
      (node (ref "P2") (pin "3") (pinfunction "3_3") (pintype "unspecified"))
      (node (ref "U1") (pin "12") (pinfunction "IO27_12") (pintype "unspecified"))
    )
    (net (code "45") (name "SERVO3") (class "Default")
      (node (ref "P4") (pin "3") (pinfunction "3_3") (pintype "unspecified"))
      (node (ref "U1") (pin "13") (pinfunction "IO14_13") (pintype "unspecified"))
    )
    (net (code "46") (name "SERVO4") (class "Default")
      (node (ref "P3") (pin "3") (pinfunction "3_3") (pintype "unspecified"))
      (node (ref "U1") (pin "16") (pinfunction "IO13_16") (pintype "unspecified"))
    )
    (net (code "47") (name "SERVO_PWR") (class "Default")
      (node (ref "P1") (pin "2") (pinfunction "2_2") (pintype "unspecified"))
      (node (ref "P2") (pin "2") (pinfunction "2_2") (pintype "unspecified"))
      (node (ref "P3") (pin "2") (pinfunction "2_2") (pintype "unspecified"))
      (node (ref "P4") (pin "2") (pinfunction "2_2") (pintype "unspecified"))
      (node (ref "SW3") (pin "2") (pinfunction "2_2") (pintype "unspecified"))
      (node (ref "U6") (pin "3") (pinfunction "VIN_3") (pintype "unspecified"))
    )
    (net (code "48") (name "SPI1_SCK") (class "Default")
      (node (ref "CARD1") (pin "5") (pinfunction "CLX_5") (pintype "unspecified"))
      (node (ref "U1") (pin "8") (pinfunction "IO32_8") (pintype "unspecified"))
      (node (ref "U2") (pin "2") (pinfunction "SCK_2") (pintype "unspecified"))
    )
    (net (code "49") (name "SPI1_SDI") (class "Default")
      (node (ref "CARD1") (pin "3") (pinfunction "CMD_3") (pintype "unspecified"))
      (node (ref "U1") (pin "9") (pinfunction "IO33_9") (pintype "unspecified"))
      (node (ref "U2") (pin "4") (pinfunction "SDI_4") (pintype "unspecified"))
    )
    (net (code "50") (name "SPI1_SDO") (class "Default")
      (node (ref "CARD1") (pin "7") (pinfunction "DAT0_7") (pintype "unspecified"))
      (node (ref "U1") (pin "7") (pinfunction "IO35_7") (pintype "unspecified"))
      (node (ref "U2") (pin "5") (pinfunction "SDO_5") (pintype "unspecified"))
    )
    (net (code "51") (name "SPI2_SCK") (class "Default")
      (node (ref "U1") (pin "27") (pinfunction "IO16_27") (pintype "unspecified"))
      (node (ref "U3") (pin "13") (pinfunction "SCX_13") (pintype "unspecified"))
      (node (ref "U4") (pin "8") (pinfunction "SCL/SCK_8") (pintype "unspecified"))
      (node (ref "U8") (pin "1") (pinfunction "SCL/SPC_1") (pintype "unspecified"))
    )
    (net (code "52") (name "SPI2_SDI") (class "Default")
      (node (ref "U1") (pin "33") (pinfunction "IO21_33") (pintype "unspecified"))
      (node (ref "U3") (pin "14") (pinfunction "SDX_14") (pintype "unspecified"))
      (node (ref "U4") (pin "9") (pinfunction "SDA/SDI_9") (pintype "unspecified"))
      (node (ref "U8") (pin "11") (pinfunction "SDA/SDI/SDO_11") (pintype "unspecified"))
    )
    (net (code "53") (name "SPI2_SDO") (class "Default")
      (node (ref "U1") (pin "28") (pinfunction "IO17_28") (pintype "unspecified"))
      (node (ref "U3") (pin "1") (pinfunction "SDO_1") (pintype "unspecified"))
      (node (ref "U4") (pin "10") (pinfunction "SDO2_10") (pintype "unspecified"))
      (node (ref "U4") (pin "15") (pinfunction "SDO1_15") (pintype "unspecified"))
      (node (ref "U8") (pin "9") (pinfunction "SD0/SA1_9") (pintype "unspecified"))
    )
    (net (code "54") (name "TXD") (class "Default")
      (node (ref "R7") (pin "2") (pinfunction "2_2") (pintype "input"))
      (node (ref "U10") (pin "26") (pinfunction "TXD_26") (pintype "unspecified"))
    )
    (net (code "55") (name "TXD0") (class "Default")
      (node (ref "R6") (pin "1") (pinfunction "1_1") (pintype "input"))
      (node (ref "U1") (pin "35") (pinfunction "TXD0_35") (pintype "unspecified"))
    )
    (net (code "56") (name "VBUS") (class "Default")
      (node (ref "D2") (pin "2") (pinfunction "K_2") (pintype "unspecified"))
      (node (ref "D3") (pin "2") (pinfunction "K_2") (pintype "unspecified"))
      (node (ref "R12") (pin "2") (pinfunction "2_2") (pintype "input"))
      (node (ref "SW3") (pin "3") (pinfunction "3_3") (pintype "unspecified"))
    )
    (net (code "57") (name "unconnected-(CARD1-DAT1-Pad8)") (class "Default")
      (node (ref "CARD1") (pin "8") (pinfunction "DAT1_8") (pintype "unspecified+no_connect"))
    )
    (net (code "58") (name "unconnected-(CARD1-DAT2-Pad1)") (class "Default")
      (node (ref "CARD1") (pin "1") (pinfunction "DAT2_1") (pintype "unspecified+no_connect"))
    )
    (net (code "59") (name "unconnected-(SW1-Pad1)") (class "Default")
      (node (ref "SW1") (pin "1") (pinfunction "1_1") (pintype "unspecified"))
    )
    (net (code "60") (name "unconnected-(SW1-Pad4)") (class "Default")
      (node (ref "SW1") (pin "4") (pinfunction "4_4") (pintype "unspecified"))
    )
    (net (code "61") (name "unconnected-(SW2-Pad1)") (class "Default")
      (node (ref "SW2") (pin "1") (pinfunction "1_1") (pintype "unspecified"))
    )
    (net (code "62") (name "unconnected-(SW2-Pad4)") (class "Default")
      (node (ref "SW2") (pin "4") (pinfunction "4_4") (pintype "unspecified"))
    )
    (net (code "63") (name "unconnected-(SW3-Pad1)") (class "Default")
      (node (ref "SW3") (pin "1") (pinfunction "1_1") (pintype "unspecified"))
    )
    (net (code "64") (name "unconnected-(U1-IO12-Pad14)") (class "Default")
      (node (ref "U1") (pin "14") (pinfunction "IO12_14") (pintype "unspecified+no_connect"))
    )
    (net (code "65") (name "unconnected-(U1-NC-Pad17)") (class "Default")
      (node (ref "U1") (pin "17") (pinfunction "NC_17") (pintype "unspecified+no_connect"))
    )
    (net (code "66") (name "unconnected-(U1-NC-Pad18)") (class "Default")
      (node (ref "U1") (pin "18") (pinfunction "NC_18") (pintype "unspecified+no_connect"))
    )
    (net (code "67") (name "unconnected-(U1-NC-Pad19)") (class "Default")
      (node (ref "U1") (pin "19") (pinfunction "NC_19") (pintype "unspecified+no_connect"))
    )
    (net (code "68") (name "unconnected-(U1-NC-Pad20)") (class "Default")
      (node (ref "U1") (pin "20") (pinfunction "NC_20") (pintype "unspecified+no_connect"))
    )
    (net (code "69") (name "unconnected-(U1-NC-Pad21)") (class "Default")
      (node (ref "U1") (pin "21") (pinfunction "NC_21") (pintype "unspecified+no_connect"))
    )
    (net (code "70") (name "unconnected-(U1-NC-Pad22)") (class "Default")
      (node (ref "U1") (pin "22") (pinfunction "NC_22") (pintype "unspecified+no_connect"))
    )
    (net (code "71") (name "unconnected-(U1-NC-Pad32)") (class "Default")
      (node (ref "U1") (pin "32") (pinfunction "NC_32") (pintype "unspecified+no_connect"))
    )
    (net (code "72") (name "unconnected-(U3-ASCX-Pad3)") (class "Default")
      (node (ref "U3") (pin "3") (pinfunction "ASCX_3") (pintype "unspecified+no_connect"))
    )
    (net (code "73") (name "unconnected-(U3-ASDX-Pad2)") (class "Default")
      (node (ref "U3") (pin "2") (pinfunction "ASDX_2") (pintype "unspecified+no_connect"))
    )
    (net (code "74") (name "unconnected-(U3-OCSB-Pad10)") (class "Default")
      (node (ref "U3") (pin "10") (pinfunction "OCSB_10") (pintype "unspecified+no_connect"))
    )
    (net (code "75") (name "unconnected-(U3-OSDO-Pad11)") (class "Default")
      (node (ref "U3") (pin "11") (pinfunction "OSDO_11") (pintype "unspecified+no_connect"))
    )
    (net (code "76") (name "unconnected-(U4-GNDA-Pad4)") (class "Default")
      (node (ref "U4") (pin "4") (pinfunction "GNDA_4") (pintype "unspecified"))
    )
    (net (code "77") (name "unconnected-(U5-CSB-Pad1)") (class "Default")
      (node (ref "U5") (pin "1") (pinfunction "CSB_1") (pintype "unspecified+no_connect"))
    )
    (net (code "78") (name "unconnected-(U5-INT-Pad7)") (class "Default")
      (node (ref "U5") (pin "7") (pinfunction "INT_7") (pintype "unspecified+no_connect"))
    )
    (net (code "79") (name "unconnected-(U5-RESV-Pad8)") (class "Default")
      (node (ref "U5") (pin "8") (pinfunction "RESV_8") (pintype "unspecified+no_connect"))
    )
    (net (code "80") (name "unconnected-(U5-RESV-Pad9)") (class "Default")
      (node (ref "U5") (pin "9") (pinfunction "RESV_9") (pintype "unspecified+no_connect"))
    )
    (net (code "81") (name "unconnected-(U5-SCL-Pad2)") (class "Default")
      (node (ref "U5") (pin "2") (pinfunction "SCL_2") (pintype "unspecified+no_connect"))
    )
    (net (code "82") (name "unconnected-(U5-SDA{slash}SDIO{slash}SDI-Pad4)") (class "Default")
      (node (ref "U5") (pin "4") (pinfunction "SDA/SDIO/SDI_4") (pintype "unspecified+no_connect"))
    )
    (net (code "83") (name "unconnected-(U5-SDO{slash}AD0-Pad6)") (class "Default")
      (node (ref "U5") (pin "6") (pinfunction "SDO/AD0_6") (pintype "unspecified+no_connect"))
    )
    (net (code "84") (name "unconnected-(U5-VDD-Pad5)") (class "Default")
      (node (ref "U5") (pin "5") (pinfunction "VDD_5") (pintype "unspecified+no_connect"))
    )
    (net (code "85") (name "unconnected-(U5-VDDIO-Pad10)") (class "Default")
      (node (ref "U5") (pin "10") (pinfunction "VDDIO_10") (pintype "unspecified+no_connect"))
    )
    (net (code "86") (name "unconnected-(U5-VSS-Pad3)") (class "Default")
      (node (ref "U5") (pin "3") (pinfunction "VSS_3") (pintype "unspecified+no_connect"))
    )
    (net (code "87") (name "unconnected-(U6-VOUT-Pad4)") (class "Default")
      (node (ref "U6") (pin "4") (pinfunction "VOUT_4") (pintype "unspecified"))
    )
    (net (code "88") (name "unconnected-(U8-DRDY-Pad8)") (class "Default")
      (node (ref "U8") (pin "8") (pinfunction "DRDY_8") (pintype "unspecified+no_connect"))
    )
    (net (code "89") (name "unconnected-(U10-CTS-Pad23)") (class "Default")
      (node (ref "U10") (pin "23") (pinfunction "CTS_23") (pintype "unspecified+no_connect"))
    )
    (net (code "90") (name "unconnected-(U10-DCD-Pad1)") (class "Default")
      (node (ref "U10") (pin "1") (pinfunction "DCD_1") (pintype "unspecified+no_connect"))
    )
    (net (code "91") (name "unconnected-(U10-DSR-Pad27)") (class "Default")
      (node (ref "U10") (pin "27") (pinfunction "DSR_27") (pintype "unspecified+no_connect"))
    )
    (net (code "92") (name "unconnected-(U10-NC-Pad10)") (class "Default")
      (node (ref "U10") (pin "10") (pinfunction "NC_10") (pintype "unspecified+no_connect"))
    )
    (net (code "93") (name "unconnected-(U10-NC-Pad13)") (class "Default")
      (node (ref "U10") (pin "13") (pinfunction "NC_13") (pintype "unspecified+no_connect"))
    )
    (net (code "94") (name "unconnected-(U10-NC-Pad14)") (class "Default")
      (node (ref "U10") (pin "14") (pinfunction "NC_14") (pintype "unspecified+no_connect"))
    )
    (net (code "95") (name "unconnected-(U10-NC-Pad15)") (class "Default")
      (node (ref "U10") (pin "15") (pinfunction "NC_15") (pintype "unspecified+no_connect"))
    )
    (net (code "96") (name "unconnected-(U10-NC-Pad16)") (class "Default")
      (node (ref "U10") (pin "16") (pinfunction "NC_16") (pintype "unspecified+no_connect"))
    )
    (net (code "97") (name "unconnected-(U10-NC-Pad17)") (class "Default")
      (node (ref "U10") (pin "17") (pinfunction "NC_17") (pintype "unspecified+no_connect"))
    )
    (net (code "98") (name "unconnected-(U10-NC-Pad18)") (class "Default")
      (node (ref "U10") (pin "18") (pinfunction "NC_18") (pintype "unspecified+no_connect"))
    )
    (net (code "99") (name "unconnected-(U10-NC-Pad19)") (class "Default")
      (node (ref "U10") (pin "19") (pinfunction "NC_19") (pintype "unspecified+no_connect"))
    )
    (net (code "100") (name "unconnected-(U10-NC-Pad20)") (class "Default")
      (node (ref "U10") (pin "20") (pinfunction "NC_20") (pintype "unspecified+no_connect"))
    )
    (net (code "101") (name "unconnected-(U10-NC-Pad21)") (class "Default")
      (node (ref "U10") (pin "21") (pinfunction "NC_21") (pintype "unspecified+no_connect"))
    )
    (net (code "102") (name "unconnected-(U10-NC-Pad22)") (class "Default")
      (node (ref "U10") (pin "22") (pinfunction "NC_22") (pintype "unspecified+no_connect"))
    )
    (net (code "103") (name "unconnected-(U10-RI-Pad2)") (class "Default")
      (node (ref "U10") (pin "2") (pinfunction "RI_2") (pintype "unspecified+no_connect"))
    )
    (net (code "104") (name "unconnected-(U10-SUSPEND#-Pad11)") (class "Default")
      (node (ref "U10") (pin "11") (pinfunction "SUSPEND#_11") (pintype "unspecified+no_connect"))
    )
    (net (code "105") (name "unconnected-(U10-SUSPEND-Pad12)") (class "Default")
      (node (ref "U10") (pin "12") (pinfunction "SUSPEND_12") (pintype "unspecified+no_connect"))
    )
    (net (code "106") (name "unconnected-(USB1-ID-Pad4)") (class "Default")
      (node (ref "USB1") (pin "4") (pinfunction "ID_4") (pintype "unspecified+no_connect"))
    )
  )
)
